# ace128_pcf8574_qwiic_v1.net
KiCad netlist of a schematic drawn in EAGLE
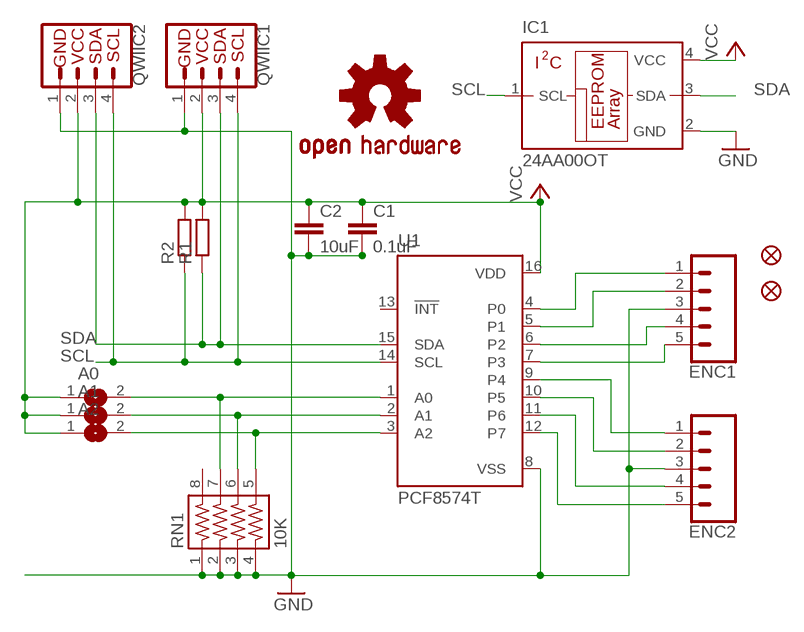
[diagram p0: schematic, sheet 1]

(export (version "E")
  (design (tool "Eeschema 10.0.6"))
  (components
    (comp (ref "A0") (value "SJ") (footprint "eagle-import:SJ") (libsource (lib "eagle-import") (part "SJ")))
    (comp (ref "A1") (value "SJ") (footprint "eagle-import:SJ") (libsource (lib "eagle-import") (part "SJ")))
    (comp (ref "A2") (value "SJ") (footprint "eagle-import:SJ") (libsource (lib "eagle-import") (part "SJ")))
    (comp (ref "C1")
      (value "0.1uF")
      (footprint "eagle-import:C0603")
      (libsource (lib "eagle-import") (part "rcl_334_C-EUC0603"))
    )
    (comp (ref "C2")
      (value "10uF")
      (footprint "eagle-import:C0805")
      (libsource (lib "eagle-import") (part "C-EUC0805"))
    )
    (comp (ref "ENC1")
      (value "CONN_05")
      (footprint "eagle-import:1X05")
      (libsource (lib "eagle-import") (part "CONN_05"))
    )
    (comp (ref "ENC2")
      (value "CONN_05")
      (footprint "eagle-import:1X05")
      (libsource (lib "eagle-import") (part "CONN_05"))
    )
    (comp (ref "FD1")
      (value "FIDUCIAL1X2")
      (footprint "eagle-import:FIDUCIAL-1X2")
      (libsource (lib "eagle-import") (part "FIDUCIAL1X2"))
    )
    (comp (ref "FD2")
      (value "FIDUCIAL1X2")
      (footprint "eagle-import:FIDUCIAL-1X2")
      (libsource (lib "eagle-import") (part "FIDUCIAL1X2"))
    )
    (comp (ref "IC1")
      (value "24AA00OT")
      (footprint "eagle-import:SOT23-5L")
      (fields (field (name "MF") "MICROCHIP") (field (name "MPN") "24AA00T-I/OTG"))
      (libsource (lib "eagle-import") (part "2400OTAA"))
    )
    (comp (ref "LOGO1")
      (value "OSHW-LOGOS")
      (footprint "eagle-import:OSHW-LOGO-S")
      (libsource (lib "eagle-import") (part "OSHW-LOGOS"))
    )
    (comp (ref "QWIIC1")
      (value "QWIIC_CONNECTORJS-1MM")
      (footprint "eagle-import:1X04_1MM_RA")
      (libsource (lib "eagle-import") (part "QWIIC_CONNECTORJS-1MM"))
    )
    (comp (ref "QWIIC2")
      (value "QWIIC_CONNECTORJS-1MM")
      (footprint "eagle-import:1X04_1MM_RA")
      (libsource (lib "eagle-import") (part "QWIIC_CONNECTORJS-1MM"))
    )
    (comp (ref "R1")
      (value "R-EU_0207/2V")
      (footprint "eagle-import:0207_2V")
      (libsource (lib "eagle-import") (part "R-EU_0207/2V"))
    )
    (comp (ref "R2")
      (value "R-EU_0207/2V")
      (footprint "eagle-import:0207_2V")
      (libsource (lib "eagle-import") (part "R-EU_0207/2V"))
    )
    (comp (ref "RN1")
      (value "10K")
      (footprint "eagle-import:743-8")
      (libsource (lib "eagle-import") (part "743-8"))
    )
    (comp (ref "U1")
      (value "PCF8574T")
      (footprint "eagle-import:SO16W")
      (fields (field (name "MPN") "PCF8574T/3,512"))
      (libsource (lib "eagle-import") (part "PCF8574T"))
    )
  )
  (nets
    (net (code "1") (name "/SCL") (class "Default")
      (node (ref "IC1") (pin "1") (pinfunction "SCL_1") (pintype "input"))
      (node (ref "QWIIC1") (pin "4") (pinfunction "SCL_4") (pintype "passive"))
      (node (ref "QWIIC2") (pin "4") (pinfunction "SCL_4") (pintype "passive"))
      (node (ref "R2") (pin "1") (pinfunction "1_1") (pintype "passive"))
      (node (ref "U1") (pin "14") (pinfunction "SCL_14") (pintype "input"))
    )
    (net (code "2") (name "/SDA") (class "Default")
      (node (ref "IC1") (pin "3") (pinfunction "SDA_3") (pintype "bidirectional"))
      (node (ref "QWIIC1") (pin "3") (pinfunction "SDA_3") (pintype "passive"))
      (node (ref "QWIIC2") (pin "3") (pinfunction "SDA_3") (pintype "passive"))
      (node (ref "R1") (pin "1") (pinfunction "1_1") (pintype "passive"))
      (node (ref "U1") (pin "15") (pinfunction "SDA_15") (pintype "bidirectional"))
    )
    (net (code "3") (name "GND") (class "Default")
      (node (ref "C1") (pin "2") (pinfunction "2_2") (pintype "passive"))
      (node (ref "C2") (pin "2") (pinfunction "2_2") (pintype "passive"))
      (node (ref "ENC1") (pin "3") (pinfunction "3_3") (pintype "passive"))
      (node (ref "ENC2") (pin "3") (pinfunction "3_3") (pintype "passive"))
      (node (ref "IC1") (pin "2") (pinfunction "GND_2") (pintype "power_in"))
      (node (ref "QWIIC1") (pin "1") (pinfunction "GND_1") (pintype "power_in"))
      (node (ref "QWIIC2") (pin "1") (pinfunction "GND_1") (pintype "power_in"))
      (node (ref "RN1") (pin "1") (pinfunction "1_1") (pintype "passive"))
      (node (ref "RN1") (pin "2") (pinfunction "2_2") (pintype "passive"))
      (node (ref "RN1") (pin "3") (pinfunction "3_3") (pintype "passive"))
      (node (ref "RN1") (pin "4") (pinfunction "4_4") (pintype "passive"))
      (node (ref "U1") (pin "8") (pinfunction "VSS_8") (pintype "power_in"))
    )
    (net (code "4") (name "Net-(U1-A0)") (class "Default")
      (node (ref "A0") (pin "2") (pinfunction "2_2") (pintype "passive"))
      (node (ref "RN1") (pin "7") (pinfunction "7_7") (pintype "passive"))
      (node (ref "U1") (pin "1") (pinfunction "A0_1") (pintype "input"))
    )
    (net (code "5") (name "Net-(U1-A1)") (class "Default")
      (node (ref "A1") (pin "2") (pinfunction "2_2") (pintype "passive"))
      (node (ref "RN1") (pin "6") (pinfunction "6_6") (pintype "passive"))
      (node (ref "U1") (pin "2") (pinfunction "A1_2") (pintype "input"))
    )
    (net (code "6") (name "Net-(U1-A2)") (class "Default")
      (node (ref "A2") (pin "2") (pinfunction "2_2") (pintype "passive"))
      (node (ref "RN1") (pin "5") (pinfunction "5_5") (pintype "passive"))
      (node (ref "U1") (pin "3") (pinfunction "A2_3") (pintype "input"))
    )
    (net (code "7") (name "Net-(U1-P0)") (class "Default")
      (node (ref "ENC1") (pin "1") (pinfunction "1_1") (pintype "passive"))
      (node (ref "U1") (pin "4") (pinfunction "P0_4") (pintype "bidirectional"))
    )
    (net (code "8") (name "Net-(U1-P1)") (class "Default")
      (node (ref "ENC1") (pin "2") (pinfunction "2_2") (pintype "passive"))
      (node (ref "U1") (pin "5") (pinfunction "P1_5") (pintype "bidirectional"))
    )
    (net (code "9") (name "Net-(U1-P2)") (class "Default")
      (node (ref "ENC1") (pin "4") (pinfunction "4_4") (pintype "passive"))
      (node (ref "U1") (pin "6") (pinfunction "P2_6") (pintype "bidirectional"))
    )
    (net (code "10") (name "Net-(U1-P3)") (class "Default")
      (node (ref "ENC1") (pin "5") (pinfunction "5_5") (pintype "passive"))
      (node (ref "U1") (pin "7") (pinfunction "P3_7") (pintype "bidirectional"))
    )
    (net (code "11") (name "Net-(U1-P4)") (class "Default")
      (node (ref "ENC2") (pin "1") (pinfunction "1_1") (pintype "passive"))
      (node (ref "U1") (pin "9") (pinfunction "P4_9") (pintype "bidirectional"))
    )
    (net (code "12") (name "Net-(U1-P5)") (class "Default")
      (node (ref "ENC2") (pin "2") (pinfunction "2_2") (pintype "passive"))
      (node (ref "U1") (pin "10") (pinfunction "P5_10") (pintype "bidirectional"))
    )
    (net (code "13") (name "Net-(U1-P6)") (class "Default")
      (node (ref "ENC2") (pin "4") (pinfunction "4_4") (pintype "passive"))
      (node (ref "U1") (pin "11") (pinfunction "P6_11") (pintype "bidirectional"))
    )
    (net (code "14") (name "Net-(U1-P7)") (class "Default")
      (node (ref "ENC2") (pin "5") (pinfunction "5_5") (pintype "passive"))
      (node (ref "U1") (pin "12") (pinfunction "P7_12") (pintype "bidirectional"))
    )
    (net (code "15") (name "VCC") (class "Default")
      (node (ref "A0") (pin "1") (pinfunction "1_1") (pintype "passive"))
      (node (ref "A1") (pin "1") (pinfunction "1_1") (pintype "passive"))
      (node (ref "A2") (pin "1") (pinfunction "1_1") (pintype "passive"))
      (node (ref "C1") (pin "1") (pinfunction "1_1") (pintype "passive"))
      (node (ref "C2") (pin "1") (pinfunction "1_1") (pintype "passive"))
      (node (ref "IC1") (pin "4") (pinfunction "VCC_4") (pintype "power_in"))
      (node (ref "QWIIC1") (pin "2") (pinfunction "VCC_2") (pintype "power_in"))
      (node (ref "QWIIC2") (pin "2") (pinfunction "VCC_2") (pintype "power_in"))
      (node (ref "R1") (pin "2") (pinfunction "2_2") (pintype "passive"))
      (node (ref "R2") (pin "2") (pinfunction "2_2") (pintype "passive"))
      (node (ref "U1") (pin "16") (pinfunction "VDD_16") (pintype "power_in"))
    )
    (net (code "16") (name "unconnected-(RN1-Pad8)") (class "Default")
      (node (ref "RN1") (pin "8") (pinfunction "8_8") (pintype "passive"))
    )
    (net (code "17") (name "unconnected-(U1-~{INT}-Pad13)") (class "Default")
      (node (ref "U1") (pin "13") (pinfunction "~{INT}_13") (pintype "output"))
    )
  )
)
